# sushi-wing-v3.net
KiCad netlist of a schematic drawn in EAGLE
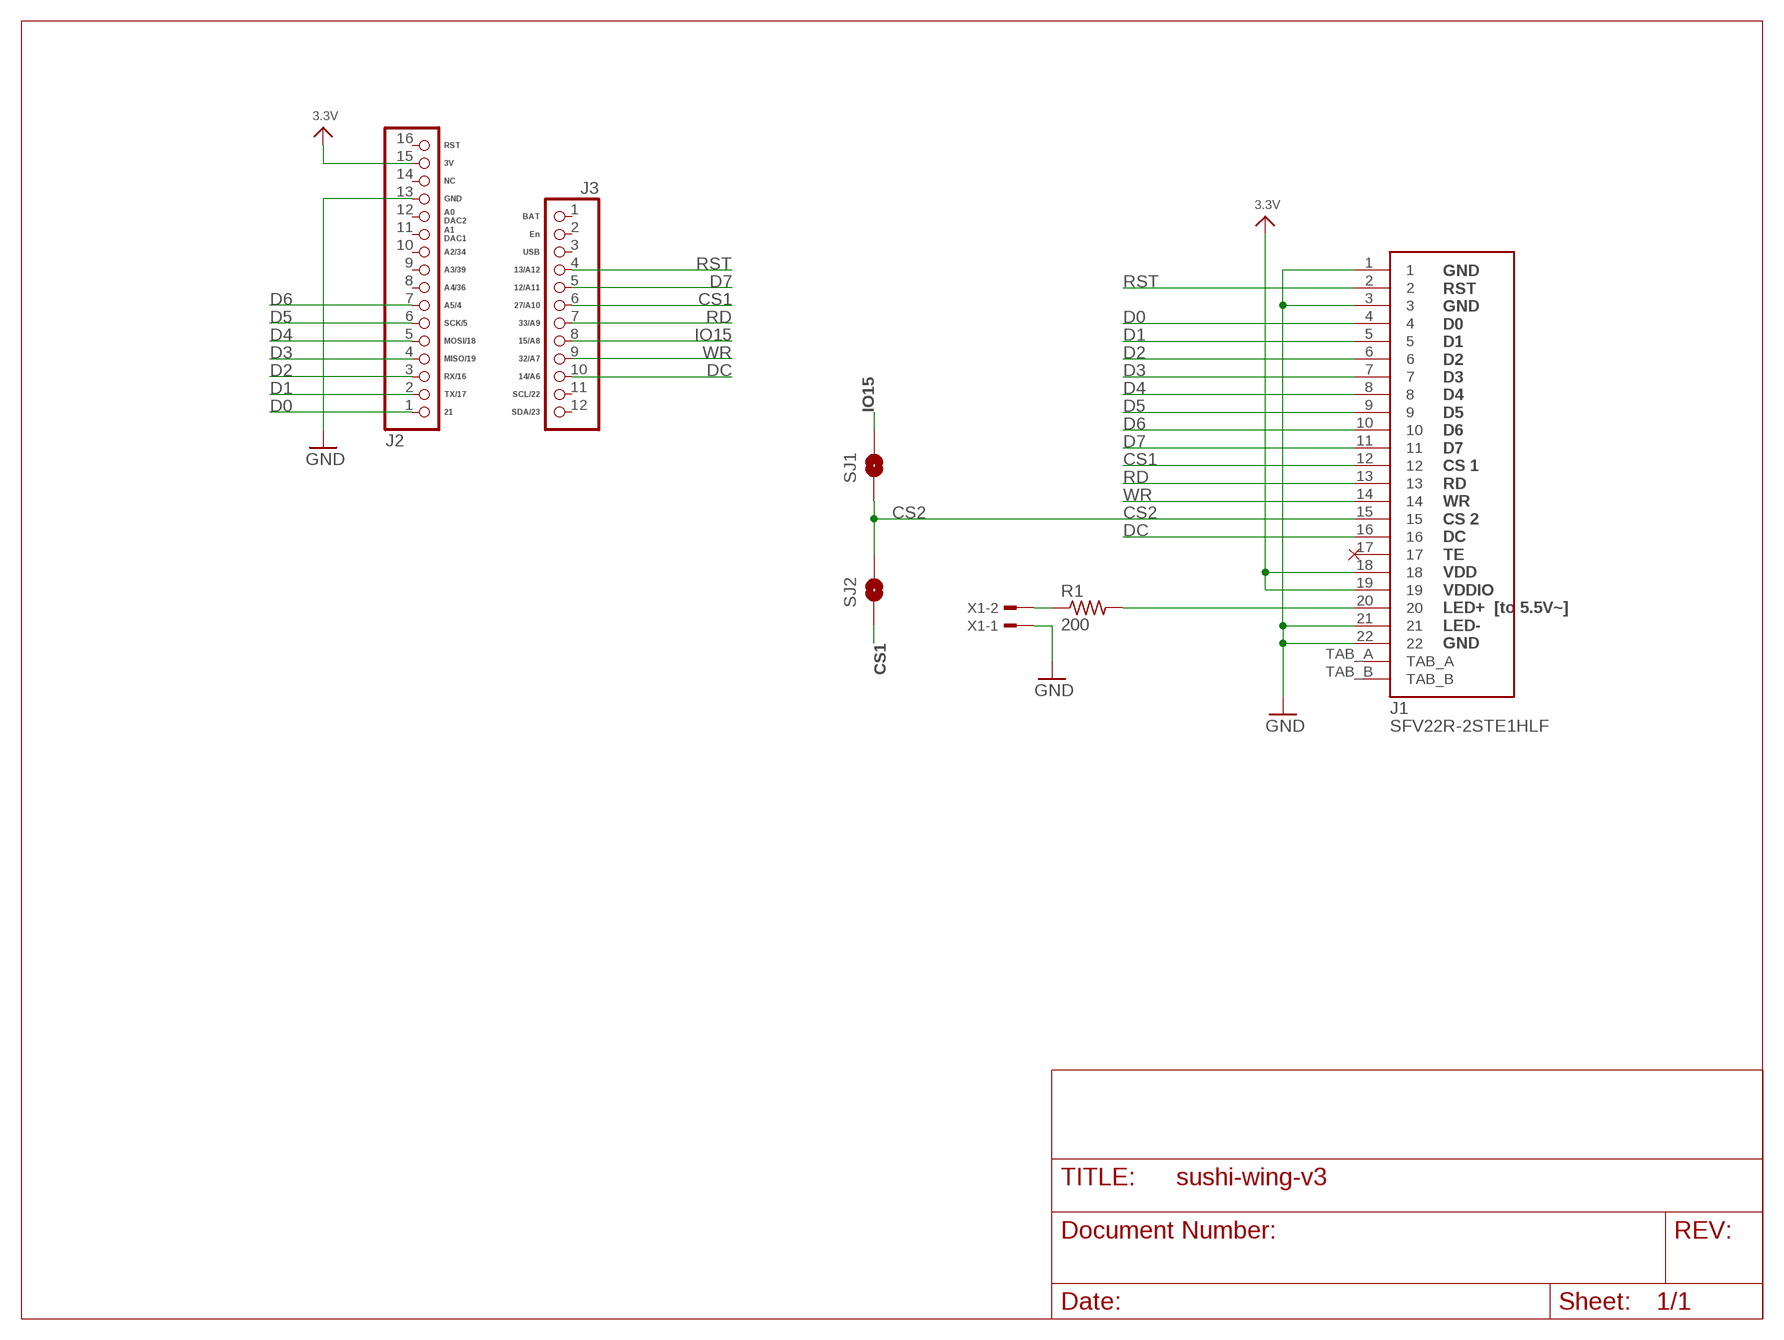
[diagram p0: schematic, sheet 1]

(export (version "E")
  (design (tool "Eeschema 10.0.6"))
  (components
    (comp (ref "J1")
      (value "SFV22R-2STE1HLF")
      (footprint "eagle-import:SFV22R-2STE1HLF")
      (libsource (lib "eagle-import") (part "SFV22R-2STE1HLF"))
    )
    (comp (ref "J2")
      (value "HEADER-1X16_MIN")
      (footprint "eagle-import:1X16_ROUND_MIN")
      (libsource (lib "eagle-import") (part "HEADER-1X16_MIN"))
    )
    (comp (ref "J3")
      (value "HEADER-1X12_MIN")
      (footprint "eagle-import:1X12_ROUND_MIN")
      (libsource (lib "eagle-import") (part "HEADER-1X12_MIN"))
    )
    (comp (ref "R1")
      (value "200")
      (footprint "eagle-import:R1206")
      (libsource (lib "eagle-import") (part "R-US_R1206"))
    )
    (comp (ref "SJ1")
      (value "SOLDERJUMPERNO")
      (footprint "eagle-import:SJ_2S-NO")
      (libsource (lib "eagle-import") (part "SOLDERJUMPERNO"))
    )
    (comp (ref "SJ2")
      (value "SOLDERJUMPERNO")
      (footprint "eagle-import:SJ_2S-NO")
      (libsource (lib "eagle-import") (part "SOLDERJUMPERNO"))
    )
    (comp (ref "X1")
      (value "TSW-102-02-S-S-RA")
      (footprint "eagle-import:TSW-102-02-S-S-RA")
      (libsource (lib "eagle-import") (part "TSW-102-02-S-S-RA"))
    )
  )
  (nets
    (net (code "1") (name "/CS1") (class "Default")
      (node (ref "J1") (pin "12") (pinfunction "12_12") (pintype "bidirectional"))
      (node (ref "J3") (pin "6") (pinfunction "6_6") (pintype "passive"))
      (node (ref "SJ2") (pin "1") (pinfunction "1_1") (pintype "passive"))
    )
    (net (code "2") (name "/CS2") (class "Default")
      (node (ref "J1") (pin "15") (pinfunction "15_15") (pintype "bidirectional"))
      (node (ref "SJ1") (pin "1") (pinfunction "1_1") (pintype "passive"))
      (node (ref "SJ2") (pin "2") (pinfunction "2_2") (pintype "passive"))
    )
    (net (code "3") (name "/D0") (class "Default")
      (node (ref "J1") (pin "4") (pinfunction "4_4") (pintype "bidirectional"))
      (node (ref "J2") (pin "1") (pinfunction "1_1") (pintype "passive"))
    )
    (net (code "4") (name "/D1") (class "Default")
      (node (ref "J1") (pin "5") (pinfunction "5_5") (pintype "bidirectional"))
      (node (ref "J2") (pin "2") (pinfunction "2_2") (pintype "passive"))
    )
    (net (code "5") (name "/D2") (class "Default")
      (node (ref "J1") (pin "6") (pinfunction "6_6") (pintype "bidirectional"))
      (node (ref "J2") (pin "3") (pinfunction "3_3") (pintype "passive"))
    )
    (net (code "6") (name "/D3") (class "Default")
      (node (ref "J1") (pin "7") (pinfunction "7_7") (pintype "bidirectional"))
      (node (ref "J2") (pin "4") (pinfunction "4_4") (pintype "passive"))
    )
    (net (code "7") (name "/D4") (class "Default")
      (node (ref "J1") (pin "8") (pinfunction "8_8") (pintype "bidirectional"))
      (node (ref "J2") (pin "5") (pinfunction "5_5") (pintype "passive"))
    )
    (net (code "8") (name "/D5") (class "Default")
      (node (ref "J1") (pin "9") (pinfunction "9_9") (pintype "bidirectional"))
      (node (ref "J2") (pin "6") (pinfunction "6_6") (pintype "passive"))
    )
    (net (code "9") (name "/D6") (class "Default")
      (node (ref "J1") (pin "10") (pinfunction "10_10") (pintype "bidirectional"))
      (node (ref "J2") (pin "7") (pinfunction "7_7") (pintype "passive"))
    )
    (net (code "10") (name "/D7") (class "Default")
      (node (ref "J1") (pin "11") (pinfunction "11_11") (pintype "bidirectional"))
      (node (ref "J3") (pin "5") (pinfunction "5_5") (pintype "passive"))
    )
    (net (code "11") (name "/DC") (class "Default")
      (node (ref "J1") (pin "16") (pinfunction "16_16") (pintype "bidirectional"))
      (node (ref "J3") (pin "10") (pinfunction "10_10") (pintype "passive"))
    )
    (net (code "12") (name "/IO15") (class "Default")
      (node (ref "J3") (pin "8") (pinfunction "8_8") (pintype "passive"))
      (node (ref "SJ1") (pin "2") (pinfunction "2_2") (pintype "passive"))
    )
    (net (code "13") (name "/RD") (class "Default")
      (node (ref "J1") (pin "13") (pinfunction "13_13") (pintype "bidirectional"))
      (node (ref "J3") (pin "7") (pinfunction "7_7") (pintype "passive"))
    )
    (net (code "14") (name "/RST") (class "Default")
      (node (ref "J1") (pin "2") (pinfunction "2_2") (pintype "bidirectional"))
      (node (ref "J3") (pin "4") (pinfunction "4_4") (pintype "passive"))
    )
    (net (code "15") (name "/WR") (class "Default")
      (node (ref "J1") (pin "14") (pinfunction "14_14") (pintype "bidirectional"))
      (node (ref "J3") (pin "9") (pinfunction "9_9") (pintype "passive"))
    )
    (net (code "16") (name "3.3V") (class "Default")
      (node (ref "J1") (pin "18") (pinfunction "18_18") (pintype "bidirectional"))
      (node (ref "J1") (pin "19") (pinfunction "19_19") (pintype "bidirectional"))
      (node (ref "J2") (pin "15") (pinfunction "15_15") (pintype "passive"))
    )
    (net (code "17") (name "GND") (class "Default")
      (node (ref "J1") (pin "1") (pinfunction "1_1") (pintype "bidirectional"))
      (node (ref "J1") (pin "21") (pinfunction "21_21") (pintype "bidirectional"))
      (node (ref "J1") (pin "22") (pinfunction "22_22") (pintype "bidirectional"))
      (node (ref "J1") (pin "3") (pinfunction "3_3") (pintype "bidirectional"))
      (node (ref "J2") (pin "13") (pinfunction "13_13") (pintype "passive"))
      (node (ref "X1") (pin "1") (pinfunction "1_1") (pintype "passive"))
    )
    (net (code "18") (name "Net-(J1-Pad20)") (class "Default")
      (node (ref "J1") (pin "20") (pinfunction "20_20") (pintype "bidirectional"))
      (node (ref "R1") (pin "2") (pinfunction "2_2") (pintype "passive"))
    )
    (net (code "19") (name "Net-(X1B-1)") (class "Default")
      (node (ref "R1") (pin "1") (pinfunction "1_1") (pintype "passive"))
      (node (ref "X1") (pin "2") (pinfunction "1_2") (pintype "passive"))
    )
    (net (code "20") (name "unconnected-(J1-Pad17)") (class "Default")
      (node (ref "J1") (pin "17") (pinfunction "17_17") (pintype "bidirectional"))
    )
    (net (code "21") (name "unconnected-(J1-PadTAB_A)") (class "Default")
      (node (ref "J1") (pin "TAB_A") (pinfunction "TAB_A_TAB_A") (pintype "bidirectional"))
    )
    (net (code "22") (name "unconnected-(J1-PadTAB_B)") (class "Default")
      (node (ref "J1") (pin "TAB_B") (pinfunction "TAB_B_TAB_B") (pintype "bidirectional"))
    )
    (net (code "23") (name "unconnected-(J2-Pad8)") (class "Default")
      (node (ref "J2") (pin "8") (pinfunction "8_8") (pintype "passive"))
    )
    (net (code "24") (name "unconnected-(J2-Pad9)") (class "Default")
      (node (ref "J2") (pin "9") (pinfunction "9_9") (pintype "passive"))
    )
    (net (code "25") (name "unconnected-(J2-Pad10)") (class "Default")
      (node (ref "J2") (pin "10") (pinfunction "10_10") (pintype "passive"))
    )
    (net (code "26") (name "unconnected-(J2-Pad11)") (class "Default")
      (node (ref "J2") (pin "11") (pinfunction "11_11") (pintype "passive"))
    )
    (net (code "27") (name "unconnected-(J2-Pad12)") (class "Default")
      (node (ref "J2") (pin "12") (pinfunction "12_12") (pintype "passive"))
    )
    (net (code "28") (name "unconnected-(J2-Pad14)") (class "Default")
      (node (ref "J2") (pin "14") (pinfunction "14_14") (pintype "passive"))
    )
    (net (code "29") (name "unconnected-(J2-Pad16)") (class "Default")
      (node (ref "J2") (pin "16") (pinfunction "16_16") (pintype "passive"))
    )
    (net (code "30") (name "unconnected-(J3-Pad1)") (class "Default")
      (node (ref "J3") (pin "1") (pinfunction "1_1") (pintype "passive"))
    )
    (net (code "31") (name "unconnected-(J3-Pad2)") (class "Default")
      (node (ref "J3") (pin "2") (pinfunction "2_2") (pintype "passive"))
    )
    (net (code "32") (name "unconnected-(J3-Pad3)") (class "Default")
      (node (ref "J3") (pin "3") (pinfunction "3_3") (pintype "passive"))
    )
    (net (code "33") (name "unconnected-(J3-Pad11)") (class "Default")
      (node (ref "J3") (pin "11") (pinfunction "11_11") (pintype "passive"))
    )
    (net (code "34") (name "unconnected-(J3-Pad12)") (class "Default")
      (node (ref "J3") (pin "12") (pinfunction "12_12") (pintype "passive"))
    )
  )
)
